# TPS75501_3V3.net
KiCad netlist of a schematic drawn in Altium Designer
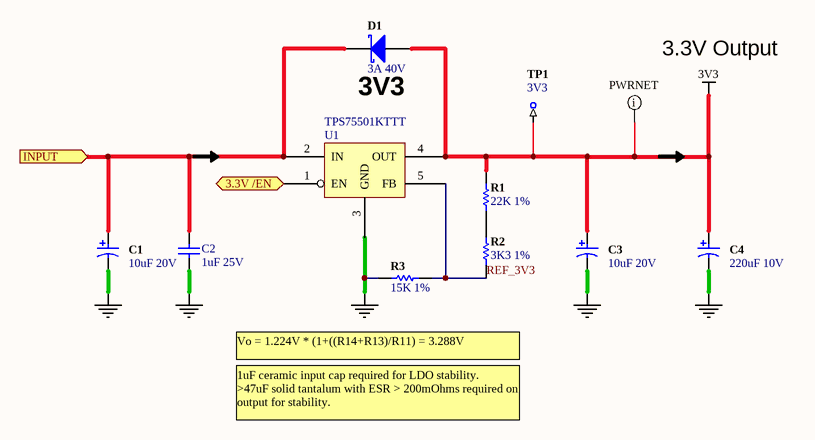
[diagram p0: TPS75501_3V3.SchDoc]

(export (version "E")
  (design (tool "Eeschema 10.0.6"))
  (components
    (comp (ref "C1")
      (value "10uF 20V")
      (footprint "CAPC3528-STAR")
      (description "Capacitor, Tantalum, 10uF 10% 20V MCCT-B (3528)")
      (fields (field (name "TOLERANCE") "10 %"))
      (libsource (lib "altium-import") (part "root_0_CAP-P_"))
    )
    (comp (ref "C2")
      (value "1uF 25V")
      (footprint "CAPC3216-STAR")
      (description "Capacitor, Ceramic, 1uF 10% 25V 1206 (3216) X7R")
      (fields (field (name "TOLERANCE") "10 %"))
      (libsource (lib "altium-import") (part "root_0_CAP-NP_"))
    )
    (comp (ref "C3")
      (value "10uF 20V")
      (footprint "CAPC3528-STAR")
      (description "Capacitor, Tantalum, 10uF 10% 20V MCCT-B (3528)")
      (fields (field (name "TOLERANCE") "10 %"))
      (libsource (lib "altium-import") (part "root_0_CAP-P_"))
    )
    (comp (ref "C4")
      (value "220uF 10V")
      (footprint "CAPC7343-STAR")
      (description "Capacitor, Tantalum, 220uF 10% 10V MCCT-D (7343-31)")
      (fields (field (name "TOLERANCE") "10 %"))
      (libsource (lib "altium-import") (part "root_0_CAP-P_"))
    )
    (comp (ref "D1")
      (value "3A 40V")
      (footprint "DIOM5027")
      (description "Schottky Diode, 3A 40V")
      (libsource (lib "altium-import") (part "root_2_DIO-SCHOTTKY-1S_"))
    )
    (comp (ref "R1")
      (value "22K 1%")
      (footprint "RESC1005-STAR")
      (description "Resistor, 22K 1% 0402 (1005)")
      (fields (field (name "TOLERANCE") "1 %"))
      (libsource (lib "altium-import") (part "root_2_RES_"))
    )
    (comp (ref "R2")
      (value "3K3 1%")
      (footprint "RESC1005-STAR")
      (description "Resistor, 3K3 1% 0402 (1005)")
      (fields (field (name "TOLERANCE") "1 %"))
      (libsource (lib "altium-import") (part "root_2_RES_"))
    )
    (comp (ref "R3")
      (value "15K 1%")
      (footprint "RESC1005-STAR")
      (description "Resistor, 15K 1% 0402 (1005)")
      (fields (field (name "TOLERANCE") "1 %"))
      (libsource (lib "altium-import") (part "root_1_RES_"))
    )
    (comp (ref "TP1")
      (value "3V3")
      (footprint "TestPin")
      (description "Test Point, PCB Mount with Silkscreen Box")
      (libsource (lib "AltiumDesignLibrary") (part "TestPin"))
    )
    (comp (ref "U1")
      (value "TPS75501KTTT")
      (footprint "TO-263")
      (description "TPS75501KTTT, 5A, Low Dropout, Adjustable, Linear Voltage Regulator, TO-263")
      (libsource (lib "altium-import") (part "root_0_TPS75501_"))
    )
  )
  (nets
    (net (code "1") (name "/3.3V {slash}EN") (class "Default")
      (node (ref "U1") (pin "1") (pinfunction "EN_1") (pintype "passive"))
    )
    (net (code "2") (name "/INPUT") (class "Default")
      (node (ref "C1") (pin "1") (pinfunction "1_1") (pintype "passive"))
      (node (ref "C2") (pin "1") (pinfunction "1_1") (pintype "passive"))
      (node (ref "D1") (pin "2") (pinfunction "K_2") (pintype "passive"))
      (node (ref "U1") (pin "2") (pinfunction "IN_2") (pintype "passive"))
    )
    (net (code "3") (name "/REF_3V3") (class "Default")
      (node (ref "R2") (pin "1") (pinfunction "1_1") (pintype "passive"))
      (node (ref "R3") (pin "2") (pinfunction "2_2") (pintype "passive"))
      (node (ref "U1") (pin "5") (pinfunction "FB_5") (pintype "passive"))
    )
    (net (code "4") (name "3V3") (class "Default")
      (node (ref "C3") (pin "1") (pinfunction "1_1") (pintype "passive"))
      (node (ref "C4") (pin "1") (pinfunction "1_1") (pintype "passive"))
      (node (ref "D1") (pin "1") (pinfunction "A_1") (pintype "passive"))
      (node (ref "R1") (pin "2") (pinfunction "2_2") (pintype "passive"))
      (node (ref "TP1") (pin "1") (pinfunction "1_1") (pintype "input"))
      (node (ref "U1") (pin "4") (pinfunction "OUT_4") (pintype "passive"))
    )
    (net (code "5") (name "GND") (class "Default")
      (node (ref "C1") (pin "2") (pinfunction "2_2") (pintype "passive"))
      (node (ref "C2") (pin "2") (pinfunction "2_2") (pintype "passive"))
      (node (ref "C3") (pin "2") (pinfunction "2_2") (pintype "passive"))
      (node (ref "C4") (pin "2") (pinfunction "2_2") (pintype "passive"))
      (node (ref "R3") (pin "1") (pinfunction "1_1") (pintype "passive"))
      (node (ref "U1") (pin "3") (pinfunction "GND_3") (pintype "passive"))
    )
    (net (code "6") (name "Net-(R1-Pad1)") (class "Default")
      (node (ref "R1") (pin "1") (pinfunction "1_1") (pintype "passive"))
      (node (ref "R2") (pin "2") (pinfunction "2_2") (pintype "passive"))
    )
  )
)
